# RibbonCable.net
KiCad netlist of a schematic drawn in Altium Designer
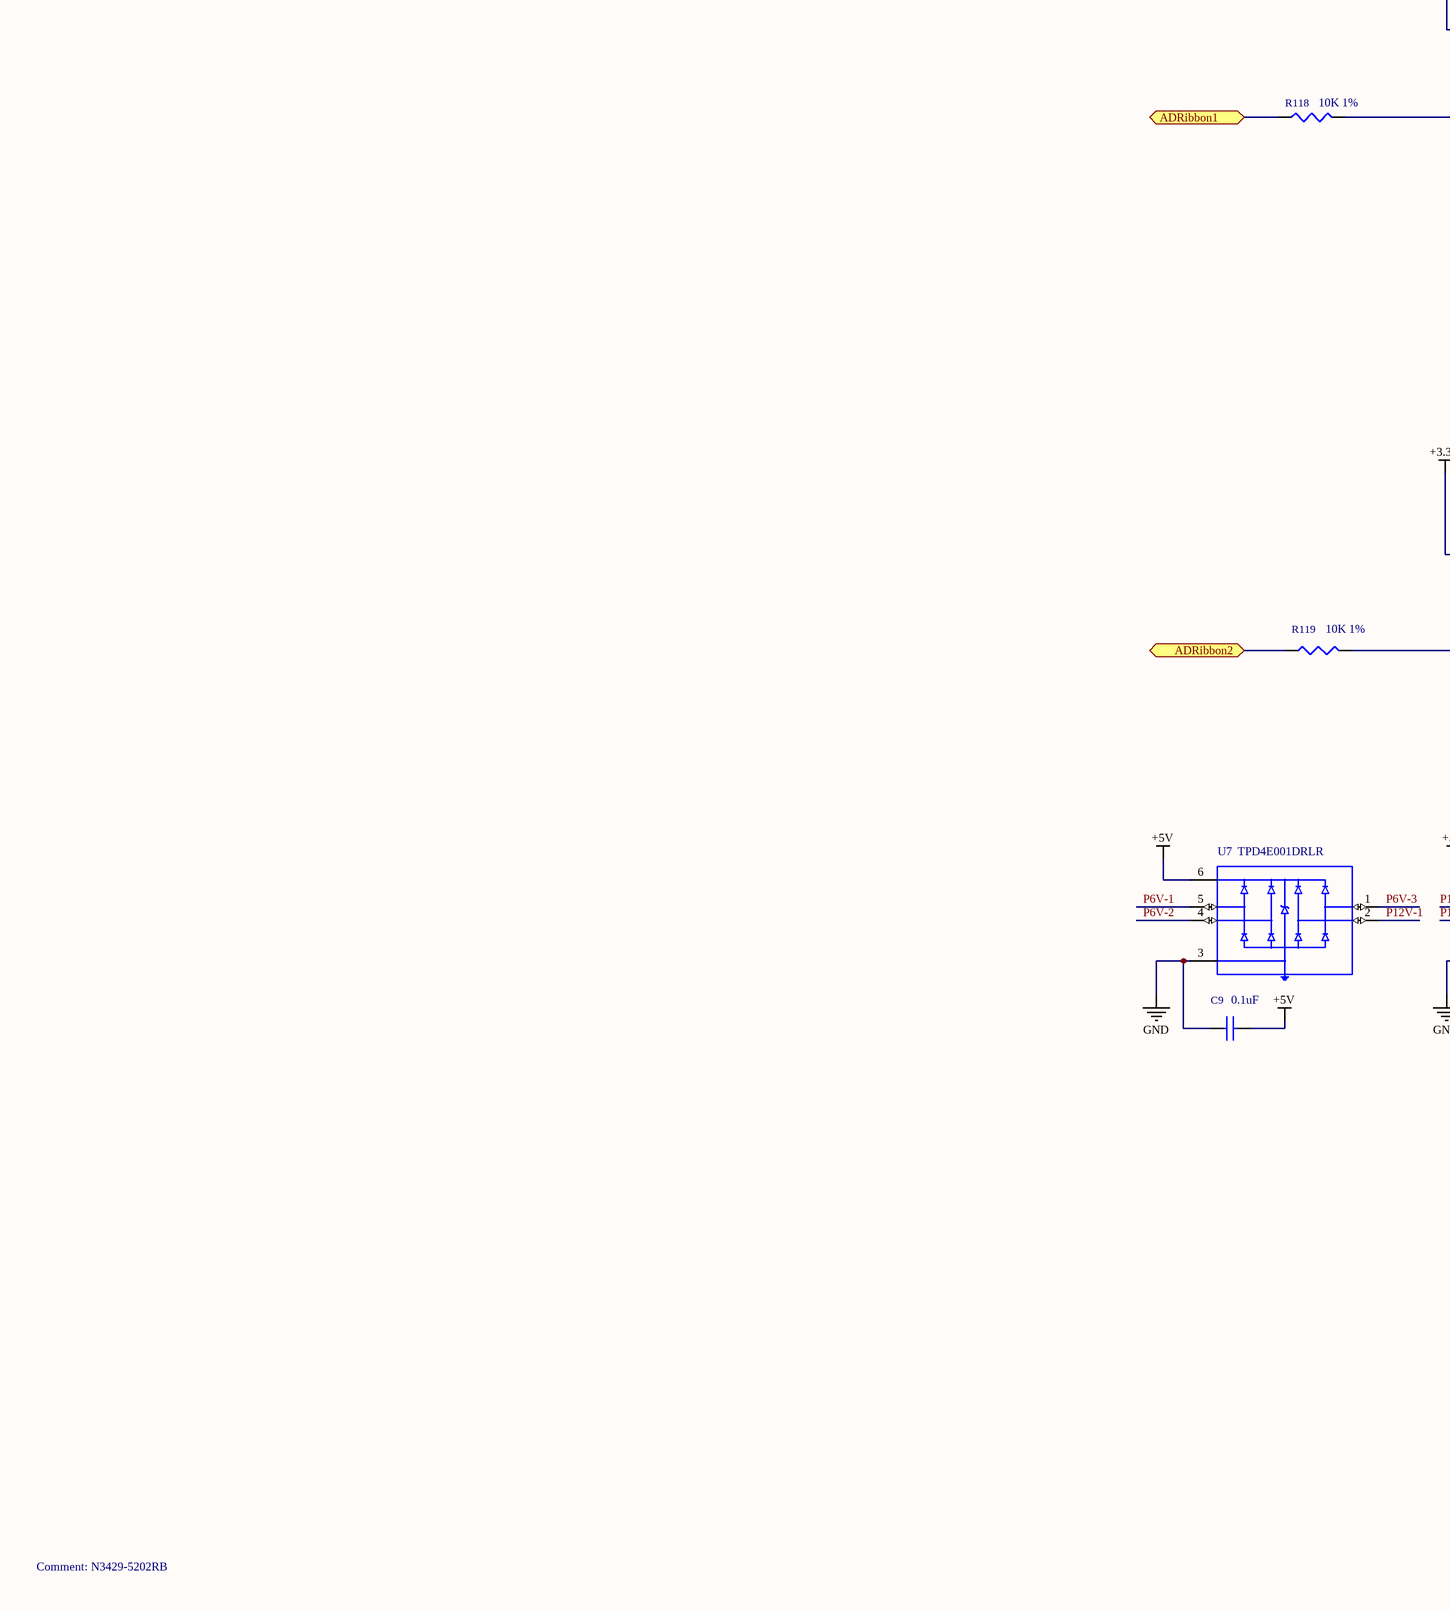
[diagram p0: RibbonCable.SchDoc, left]
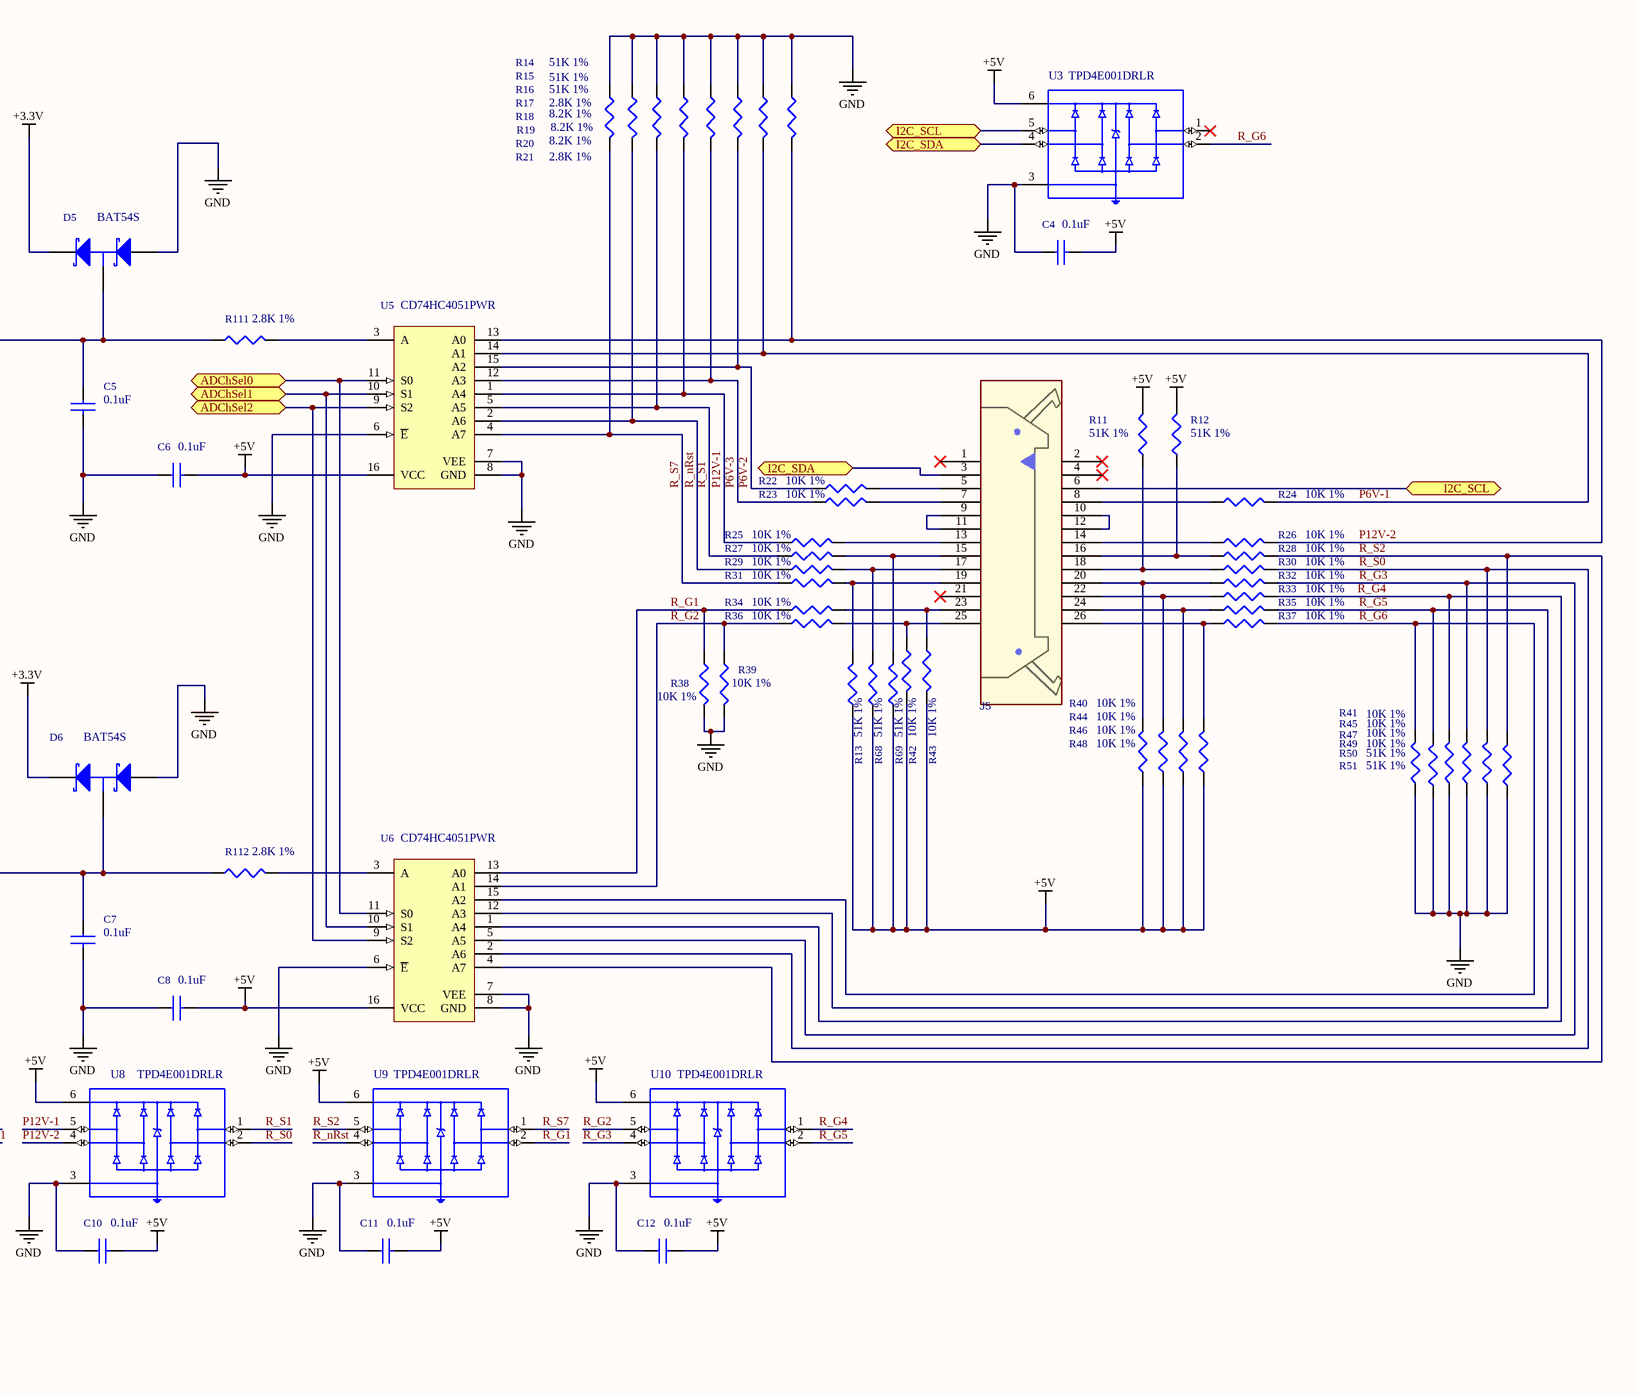
[diagram p1: RibbonCable.SchDoc, right]

(export (version "E")
  (design (tool "Eeschema 10.0.6"))
  (components
    (comp (ref "C4")
      (value "0.1uF")
      (footprint "C0402")
      (description "Cap Ceramic 0.1uF 50V X7R 10% Pad SMD 0402 125C Automotive T/R")
      (fields
        (field (name "MANUFACTURER") "Murata")
        (field (name "MANUFACTURER PART NUMBER") "GRT155R71H104KE01D")
      )
      (libsource (lib "Leo-Home-SQL-Lib") (part "CAPNP"))
    )
    (comp (ref "C5")
      (value "0.1uF")
      (footprint "C0402")
      (description "Cap Ceramic 0.1uF 50V X7R 10% Pad SMD 0402 125C Automotive T/R")
      (fields
        (field (name "MANUFACTURER") "Murata")
        (field (name "MANUFACTURER PART NUMBER") "GRT155R71H104KE01D")
      )
      (libsource (lib "Leo-Home-SQL-Lib") (part "CAPNP"))
    )
    (comp (ref "C6")
      (value "0.1uF")
      (footprint "C0402")
      (description "Cap Ceramic 0.1uF 50V X7R 10% Pad SMD 0402 125C Automotive T/R")
      (fields
        (field (name "MANUFACTURER") "Murata")
        (field (name "MANUFACTURER PART NUMBER") "GRT155R71H104KE01D")
      )
      (libsource (lib "Leo-Home-SQL-Lib") (part "CAPNP"))
    )
    (comp (ref "C7")
      (value "0.1uF")
      (footprint "C0402")
      (description "Cap Ceramic 0.1uF 50V X7R 10% Pad SMD 0402 125C Automotive T/R")
      (fields
        (field (name "MANUFACTURER") "Murata")
        (field (name "MANUFACTURER PART NUMBER") "GRT155R71H104KE01D")
      )
      (libsource (lib "Leo-Home-SQL-Lib") (part "CAPNP"))
    )
    (comp (ref "C8")
      (value "0.1uF")
      (footprint "C0402")
      (description "Cap Ceramic 0.1uF 50V X7R 10% Pad SMD 0402 125C Automotive T/R")
      (fields
        (field (name "MANUFACTURER") "Murata")
        (field (name "MANUFACTURER PART NUMBER") "GRT155R71H104KE01D")
      )
      (libsource (lib "Leo-Home-SQL-Lib") (part "CAPNP"))
    )
    (comp (ref "C9")
      (value "0.1uF")
      (footprint "C0402")
      (description "Cap Ceramic 0.1uF 50V X7R 10% Pad SMD 0402 125C Automotive T/R")
      (fields
        (field (name "MANUFACTURER") "Murata")
        (field (name "MANUFACTURER PART NUMBER") "GRT155R71H104KE01D")
      )
      (libsource (lib "Leo-Home-SQL-Lib") (part "CAPNP"))
    )
    (comp (ref "C10")
      (value "0.1uF")
      (footprint "C0402")
      (description "Cap Ceramic 0.1uF 50V X7R 10% Pad SMD 0402 125C Automotive T/R")
      (fields
        (field (name "MANUFACTURER") "Murata")
        (field (name "MANUFACTURER PART NUMBER") "GRT155R71H104KE01D")
      )
      (libsource (lib "Leo-Home-SQL-Lib") (part "CAPNP"))
    )
    (comp (ref "C11")
      (value "0.1uF")
      (footprint "C0402")
      (description "Cap Ceramic 0.1uF 50V X7R 10% Pad SMD 0402 125C Automotive T/R")
      (fields
        (field (name "MANUFACTURER") "Murata")
        (field (name "MANUFACTURER PART NUMBER") "GRT155R71H104KE01D")
      )
      (libsource (lib "Leo-Home-SQL-Lib") (part "CAPNP"))
    )
    (comp (ref "C12")
      (value "0.1uF")
      (footprint "C0402")
      (description "Cap Ceramic 0.1uF 50V X7R 10% Pad SMD 0402 125C Automotive T/R")
      (fields
        (field (name "MANUFACTURER") "Murata")
        (field (name "MANUFACTURER PART NUMBER") "GRT155R71H104KE01D")
      )
      (libsource (lib "Leo-Home-SQL-Lib") (part "CAPNP"))
    )
    (comp (ref "D5")
      (value "BAT54S")
      (footprint "sot23-3")
      (description "DIODE SCHOTTKY 30V 150MA SOT23-3")
      (fields
        (field (name "MANUFACTURER") "Sangdest Microelectronics")
        (field (name "MANUFACTURER_1") "ON Semiconductor / Fairchild")
      )
      (libsource (lib "Leo-Home-SQL-Lib") (part "BAT54S-7-F"))
    )
    (comp (ref "D6")
      (value "BAT54S")
      (footprint "sot23-3")
      (description "DIODE SCHOTTKY 30V 150MA SOT23-3")
      (fields
        (field (name "MANUFACTURER") "Sangdest Microelectronics")
        (field (name "MANUFACTURER_1") "ON Semiconductor / Fairchild")
      )
      (libsource (lib "Leo-Home-SQL-Lib") (part "BAT54S-7-F"))
    )
    (comp (ref "J5")
      (value "N3429-5202RB")
      (footprint "CONN_N3429-5202RB")
      (description "3000 Series; 2.54mm Pitch 26 Way 2 Row Right")
      (fields (field (name "MANUFACTURER") "3M") (field (name "VOLTAGE") "300V"))
      (libsource (lib "Leo-Home-SQL-Lib") (part "CN_100_26POS_13x2_RTA_LATCH"))
    )
    (comp (ref "R11")
      (value "51K 1%")
      (footprint "R0402")
      (description "Res Thick Film 0402 51K Ohm 1% 0.063W(1/16W) ±100ppm/C Pad SMD Automotive T/R")
      (fields
        (field (name "MANUFACTURER") "Stackpole Electronics")
        (field (name "MANUFACTURER PART NUMBER") "RMCF0402FT51K0")
      )
      (libsource (lib "Leo-Home-SQL-Lib") (part "Resistor"))
    )
    (comp (ref "R12")
      (value "51K 1%")
      (footprint "R0402")
      (description "Res Thick Film 0402 51K Ohm 1% 0.063W(1/16W) ±100ppm/C Pad SMD Automotive T/R")
      (fields
        (field (name "MANUFACTURER") "Stackpole Electronics")
        (field (name "MANUFACTURER PART NUMBER") "RMCF0402FT51K0")
      )
      (libsource (lib "Leo-Home-SQL-Lib") (part "Resistor"))
    )
    (comp (ref "R13")
      (value "51K 1%")
      (footprint "R0402")
      (description "Res Thick Film 0402 51K Ohm 1% 0.063W(1/16W) ±100ppm/C Pad SMD Automotive T/R")
      (fields
        (field (name "MANUFACTURER") "Stackpole Electronics")
        (field (name "MANUFACTURER PART NUMBER") "RMCF0402FT51K0")
      )
      (libsource (lib "Leo-Home-SQL-Lib") (part "Resistor"))
    )
    (comp (ref "R14")
      (value "51K 1%")
      (footprint "R0402")
      (description "Res Thick Film 0402 51K Ohm 1% 0.063W(1/16W) ±100ppm/C Pad SMD Automotive T/R")
      (fields
        (field (name "MANUFACTURER") "Stackpole Electronics")
        (field (name "MANUFACTURER PART NUMBER") "RMCF0402FT51K0")
      )
      (libsource (lib "Leo-Home-SQL-Lib") (part "Resistor"))
    )
    (comp (ref "R15")
      (value "51K 1%")
      (footprint "R0402")
      (description "Res Thick Film 0402 51K Ohm 1% 0.063W(1/16W) ±100ppm/C Pad SMD Automotive T/R")
      (fields
        (field (name "MANUFACTURER") "Stackpole Electronics")
        (field (name "MANUFACTURER PART NUMBER") "RMCF0402FT51K0")
      )
      (libsource (lib "Leo-Home-SQL-Lib") (part "Resistor"))
    )
    (comp (ref "R16")
      (value "51K 1%")
      (footprint "R0402")
      (description "Res Thick Film 0402 51K Ohm 1% 0.063W(1/16W) ±100ppm/C Pad SMD Automotive T/R")
      (fields
        (field (name "MANUFACTURER") "Stackpole Electronics")
        (field (name "MANUFACTURER PART NUMBER") "RMCF0402FT51K0")
      )
      (libsource (lib "Leo-Home-SQL-Lib") (part "Resistor"))
    )
    (comp (ref "R17")
      (value "2.8K 1%")
      (footprint "R0402")
      (description "Thick Film 0402 2.8K Ohm 1% 0.063W ±100ppm/°C Molded SMD Paper T/R")
      (fields
        (field (name "MANUFACTURER") "Stackpole Electronics")
        (field (name "MANUFACTURER PART NUMBER") "RMCF0402FT2K80")
      )
      (libsource (lib "Leo-Home-SQL-Lib") (part "Resistor"))
    )
    (comp (ref "R18")
      (value "8.2K 1%")
      (footprint "R0402")
      (description "Res Thick Film 0402 8.2K Ohm 5% 0.063W ±100ppm/°C Molded SMD Paper T/R")
      (fields
        (field (name "MANUFACTURER") "Stackpole Electronics")
        (field (name "MANUFACTURER PART NUMBER") "RMCF0402JT8K20")
      )
      (libsource (lib "Leo-Home-SQL-Lib") (part "Resistor"))
    )
    (comp (ref "R19")
      (value "8.2K 1%")
      (footprint "R0402")
      (description "Res Thick Film 0402 8.2K Ohm 5% 0.063W ±100ppm/°C Molded SMD Paper T/R")
      (fields
        (field (name "MANUFACTURER") "Stackpole Electronics")
        (field (name "MANUFACTURER PART NUMBER") "RMCF0402JT8K20")
      )
      (libsource (lib "Leo-Home-SQL-Lib") (part "Resistor"))
    )
    (comp (ref "R20")
      (value "8.2K 1%")
      (footprint "R0402")
      (description "Res Thick Film 0402 8.2K Ohm 5% 0.063W ±100ppm/°C Molded SMD Paper T/R")
      (fields
        (field (name "MANUFACTURER") "Stackpole Electronics")
        (field (name "MANUFACTURER PART NUMBER") "RMCF0402JT8K20")
      )
      (libsource (lib "Leo-Home-SQL-Lib") (part "Resistor"))
    )
    (comp (ref "R21")
      (value "2.8K 1%")
      (footprint "R0402")
      (description "Thick Film 0402 2.8K Ohm 1% 0.063W ±100ppm/°C Molded SMD Paper T/R")
      (fields
        (field (name "MANUFACTURER") "Stackpole Electronics")
        (field (name "MANUFACTURER PART NUMBER") "RMCF0402FT2K80")
      )
      (libsource (lib "Leo-Home-SQL-Lib") (part "Resistor"))
    )
    (comp (ref "R22")
      (value "10K 1%")
      (footprint "R0402")
      (description "Thick Film 0402 10K OHM 1% 1/16W 0402")
      (fields
        (field (name "MANUFACTURER") "Yageo")
        (field (name "MANUFACTURER PART NUMBER") "RC0402FR-0710KP")
      )
      (libsource (lib "Leo-Home-SQL-Lib") (part "Resistor"))
    )
    (comp (ref "R23")
      (value "10K 1%")
      (footprint "R0402")
      (description "Thick Film 0402 10K OHM 1% 1/16W 0402")
      (fields
        (field (name "MANUFACTURER") "Yageo")
        (field (name "MANUFACTURER PART NUMBER") "RC0402FR-0710KP")
      )
      (libsource (lib "Leo-Home-SQL-Lib") (part "Resistor"))
    )
    (comp (ref "R24")
      (value "10K 1%")
      (footprint "R0402")
      (description "Thick Film 0402 10K OHM 1% 1/16W 0402")
      (fields
        (field (name "MANUFACTURER") "Yageo")
        (field (name "MANUFACTURER PART NUMBER") "RC0402FR-0710KP")
      )
      (libsource (lib "Leo-Home-SQL-Lib") (part "Resistor"))
    )
    (comp (ref "R25")
      (value "10K 1%")
      (footprint "R0402")
      (description "Thick Film 0402 10K OHM 1% 1/16W 0402")
      (fields
        (field (name "MANUFACTURER") "Yageo")
        (field (name "MANUFACTURER PART NUMBER") "RC0402FR-0710KP")
      )
      (libsource (lib "Leo-Home-SQL-Lib") (part "Resistor"))
    )
    (comp (ref "R26")
      (value "10K 1%")
      (footprint "R0402")
      (description "Thick Film 0402 10K OHM 1% 1/16W 0402")
      (fields
        (field (name "MANUFACTURER") "Yageo")
        (field (name "MANUFACTURER PART NUMBER") "RC0402FR-0710KP")
      )
      (libsource (lib "Leo-Home-SQL-Lib") (part "Resistor"))
    )
    (comp (ref "R27")
      (value "10K 1%")
      (footprint "R0402")
      (description "Thick Film 0402 10K OHM 1% 1/16W 0402")
      (fields
        (field (name "MANUFACTURER") "Yageo")
        (field (name "MANUFACTURER PART NUMBER") "RC0402FR-0710KP")
      )
      (libsource (lib "Leo-Home-SQL-Lib") (part "Resistor"))
    )
    (comp (ref "R28")
      (value "10K 1%")
      (footprint "R0402")
      (description "Thick Film 0402 10K OHM 1% 1/16W 0402")
      (fields
        (field (name "MANUFACTURER") "Yageo")
        (field (name "MANUFACTURER PART NUMBER") "RC0402FR-0710KP")
      )
      (libsource (lib "Leo-Home-SQL-Lib") (part "Resistor"))
    )
    (comp (ref "R29")
      (value "10K 1%")
      (footprint "R0402")
      (description "Thick Film 0402 10K OHM 1% 1/16W 0402")
      (fields
        (field (name "MANUFACTURER") "Yageo")
        (field (name "MANUFACTURER PART NUMBER") "RC0402FR-0710KP")
      )
      (libsource (lib "Leo-Home-SQL-Lib") (part "Resistor"))
    )
    (comp (ref "R30")
      (value "10K 1%")
      (footprint "R0402")
      (description "Thick Film 0402 10K OHM 1% 1/16W 0402")
      (fields
        (field (name "MANUFACTURER") "Yageo")
        (field (name "MANUFACTURER PART NUMBER") "RC0402FR-0710KP")
      )
      (libsource (lib "Leo-Home-SQL-Lib") (part "Resistor"))
    )
    (comp (ref "R31")
      (value "10K 1%")
      (footprint "R0402")
      (description "Thick Film 0402 10K OHM 1% 1/16W 0402")
      (fields
        (field (name "MANUFACTURER") "Yageo")
        (field (name "MANUFACTURER PART NUMBER") "RC0402FR-0710KP")
      )
      (libsource (lib "Leo-Home-SQL-Lib") (part "Resistor"))
    )
    (comp (ref "R32")
      (value "10K 1%")
      (footprint "R0402")
      (description "Thick Film 0402 10K OHM 1% 1/16W 0402")
      (fields
        (field (name "MANUFACTURER") "Yageo")
        (field (name "MANUFACTURER PART NUMBER") "RC0402FR-0710KP")
      )
      (libsource (lib "Leo-Home-SQL-Lib") (part "Resistor"))
    )
    (comp (ref "R33")
      (value "10K 1%")
      (footprint "R0402")
      (description "Thick Film 0402 10K OHM 1% 1/16W 0402")
      (fields
        (field (name "MANUFACTURER") "Yageo")
        (field (name "MANUFACTURER PART NUMBER") "RC0402FR-0710KP")
      )
      (libsource (lib "Leo-Home-SQL-Lib") (part "Resistor"))
    )
    (comp (ref "R34")
      (value "10K 1%")
      (footprint "R0402")
      (description "Thick Film 0402 10K OHM 1% 1/16W 0402")
      (fields
        (field (name "MANUFACTURER") "Yageo")
        (field (name "MANUFACTURER PART NUMBER") "RC0402FR-0710KP")
      )
      (libsource (lib "Leo-Home-SQL-Lib") (part "Resistor"))
    )
    (comp (ref "R35")
      (value "10K 1%")
      (footprint "R0402")
      (description "Thick Film 0402 10K OHM 1% 1/16W 0402")
      (fields
        (field (name "MANUFACTURER") "Yageo")
        (field (name "MANUFACTURER PART NUMBER") "RC0402FR-0710KP")
      )
      (libsource (lib "Leo-Home-SQL-Lib") (part "Resistor"))
    )
    (comp (ref "R36")
      (value "10K 1%")
      (footprint "R0402")
      (description "Thick Film 0402 10K OHM 1% 1/16W 0402")
      (fields
        (field (name "MANUFACTURER") "Yageo")
        (field (name "MANUFACTURER PART NUMBER") "RC0402FR-0710KP")
      )
      (libsource (lib "Leo-Home-SQL-Lib") (part "Resistor"))
    )
    (comp (ref "R37")
      (value "10K 1%")
      (footprint "R0402")
      (description "Thick Film 0402 10K OHM 1% 1/16W 0402")
      (fields
        (field (name "MANUFACTURER") "Yageo")
        (field (name "MANUFACTURER PART NUMBER") "RC0402FR-0710KP")
      )
      (libsource (lib "Leo-Home-SQL-Lib") (part "Resistor"))
    )
    (comp (ref "R38")
      (value "10K 1%")
      (footprint "R0402")
      (description "Thick Film 0402 10K OHM 1% 1/16W 0402")
      (fields
        (field (name "MANUFACTURER") "Yageo")
        (field (name "MANUFACTURER PART NUMBER") "RC0402FR-0710KP")
      )
      (libsource (lib "Leo-Home-SQL-Lib") (part "Resistor"))
    )
    (comp (ref "R39")
      (value "10K 1%")
      (footprint "R0402")
      (description "Thick Film 0402 10K OHM 1% 1/16W 0402")
      (fields
        (field (name "MANUFACTURER") "Yageo")
        (field (name "MANUFACTURER PART NUMBER") "RC0402FR-0710KP")
      )
      (libsource (lib "Leo-Home-SQL-Lib") (part "Resistor"))
    )
    (comp (ref "R40")
      (value "10K 1%")
      (footprint "R0402")
      (description "Thick Film 0402 10K OHM 1% 1/16W 0402")
      (fields
        (field (name "MANUFACTURER") "Yageo")
        (field (name "MANUFACTURER PART NUMBER") "RC0402FR-0710KP")
      )
      (libsource (lib "Leo-Home-SQL-Lib") (part "Resistor"))
    )
    (comp (ref "R41")
      (value "10K 1%")
      (footprint "R0402")
      (description "Thick Film 0402 10K OHM 1% 1/16W 0402")
      (fields
        (field (name "MANUFACTURER") "Yageo")
        (field (name "MANUFACTURER PART NUMBER") "RC0402FR-0710KP")
      )
      (libsource (lib "Leo-Home-SQL-Lib") (part "Resistor"))
    )
    (comp (ref "R42")
      (value "10K 1%")
      (footprint "R0402")
      (description "Thick Film 0402 10K OHM 1% 1/16W 0402")
      (fields
        (field (name "MANUFACTURER") "Yageo")
        (field (name "MANUFACTURER PART NUMBER") "RC0402FR-0710KP")
      )
      (libsource (lib "Leo-Home-SQL-Lib") (part "Resistor"))
    )
    (comp (ref "R43")
      (value "10K 1%")
      (footprint "R0402")
      (description "Thick Film 0402 10K OHM 1% 1/16W 0402")
      (fields
        (field (name "MANUFACTURER") "Yageo")
        (field (name "MANUFACTURER PART NUMBER") "RC0402FR-0710KP")
      )
      (libsource (lib "Leo-Home-SQL-Lib") (part "Resistor"))
    )
    (comp (ref "R44")
      (value "10K 1%")
      (footprint "R0402")
      (description "Thick Film 0402 10K OHM 1% 1/16W 0402")
      (fields
        (field (name "MANUFACTURER") "Yageo")
        (field (name "MANUFACTURER PART NUMBER") "RC0402FR-0710KP")
      )
      (libsource (lib "Leo-Home-SQL-Lib") (part "Resistor"))
    )
    (comp (ref "R45")
      (value "10K 1%")
      (footprint "R0402")
      (description "Thick Film 0402 10K OHM 1% 1/16W 0402")
      (fields
        (field (name "MANUFACTURER") "Yageo")
        (field (name "MANUFACTURER PART NUMBER") "RC0402FR-0710KP")
      )
      (libsource (lib "Leo-Home-SQL-Lib") (part "Resistor"))
    )
    (comp (ref "R46")
      (value "10K 1%")
      (footprint "R0402")
      (description "Thick Film 0402 10K OHM 1% 1/16W 0402")
      (fields
        (field (name "MANUFACTURER") "Yageo")
        (field (name "MANUFACTURER PART NUMBER") "RC0402FR-0710KP")
      )
      (libsource (lib "Leo-Home-SQL-Lib") (part "Resistor"))
    )
    (comp (ref "R47")
      (value "10K 1%")
      (footprint "R0402")
      (description "Thick Film 0402 10K OHM 1% 1/16W 0402")
      (fields
        (field (name "MANUFACTURER") "Yageo")
        (field (name "MANUFACTURER PART NUMBER") "RC0402FR-0710KP")
      )
      (libsource (lib "Leo-Home-SQL-Lib") (part "Resistor"))
    )
    (comp (ref "R48")
      (value "10K 1%")
      (footprint "R0402")
      (description "Thick Film 0402 10K OHM 1% 1/16W 0402")
      (fields
        (field (name "MANUFACTURER") "Yageo")
        (field (name "MANUFACTURER PART NUMBER") "RC0402FR-0710KP")
      )
      (libsource (lib "Leo-Home-SQL-Lib") (part "Resistor"))
    )
    (comp (ref "R49")
      (value "10K 1%")
      (footprint "R0402")
      (description "Thick Film 0402 10K OHM 1% 1/16W 0402")
      (fields
        (field (name "MANUFACTURER") "Yageo")
        (field (name "MANUFACTURER PART NUMBER") "RC0402FR-0710KP")
      )
      (libsource (lib "Leo-Home-SQL-Lib") (part "Resistor"))
    )
    (comp (ref "R50")
      (value "51K 1%")
      (footprint "R0402")
      (description "Res Thick Film 0402 51K Ohm 1% 0.063W(1/16W) ±100ppm/C Pad SMD Automotive T/R")
      (fields
        (field (name "MANUFACTURER") "Stackpole Electronics")
        (field (name "MANUFACTURER PART NUMBER") "RMCF0402FT51K0")
      )
      (libsource (lib "Leo-Home-SQL-Lib") (part "Resistor"))
    )
    (comp (ref "R51")
      (value "51K 1%")
      (footprint "R0402")
      (description "Res Thick Film 0402 51K Ohm 1% 0.063W(1/16W) ±100ppm/C Pad SMD Automotive T/R")
      (fields
        (field (name "MANUFACTURER") "Stackpole Electronics")
        (field (name "MANUFACTURER PART NUMBER") "RMCF0402FT51K0")
      )
      (libsource (lib "Leo-Home-SQL-Lib") (part "Resistor"))
    )
    (comp (ref "R68")
      (value "51K 1%")
      (footprint "R0402")
      (description "Res Thick Film 0402 51K Ohm 1% 0.063W(1/16W) ±100ppm/C Pad SMD Automotive T/R")
      (fields
        (field (name "MANUFACTURER") "Stackpole Electronics")
        (field (name "MANUFACTURER PART NUMBER") "RMCF0402FT51K0")
      )
      (libsource (lib "Leo-Home-SQL-Lib") (part "Resistor"))
    )
    (comp (ref "R69")
      (value "51K 1%")
      (footprint "R0402")
      (description "Res Thick Film 0402 51K Ohm 1% 0.063W(1/16W) ±100ppm/C Pad SMD Automotive T/R")
      (fields
        (field (name "MANUFACTURER") "Stackpole Electronics")
        (field (name "MANUFACTURER PART NUMBER") "RMCF0402FT51K0")
      )
      (libsource (lib "Leo-Home-SQL-Lib") (part "Resistor"))
    )
    (comp (ref "R111")
      (value "2.8K 1%")
      (footprint "R0402")
      (description "Thick Film 0402 2.8K Ohm 1% 0.063W ±100ppm/°C Molded SMD Paper T/R")
      (fields
        (field (name "MANUFACTURER") "Stackpole Electronics")
        (field (name "MANUFACTURER PART NUMBER") "RMCF0402FT2K80")
      )
      (libsource (lib "Leo-Home-SQL-Lib") (part "Resistor"))
    )
    (comp (ref "R112")
      (value "2.8K 1%")
      (footprint "R0402")
      (description "Thick Film 0402 2.8K Ohm 1% 0.063W ±100ppm/°C Molded SMD Paper T/R")
      (fields
        (field (name "MANUFACTURER") "Stackpole Electronics")
        (field (name "MANUFACTURER PART NUMBER") "RMCF0402FT2K80")
      )
      (libsource (lib "Leo-Home-SQL-Lib") (part "Resistor"))
    )
    (comp (ref "R118")
      (value "10K 1%")
      (footprint "R0402")
      (description "Thick Film 0402 10K OHM 1% 1/16W 0402")
      (fields
        (field (name "MANUFACTURER") "Yageo")
        (field (name "MANUFACTURER PART NUMBER") "RC0402FR-0710KP")
      )
      (libsource (lib "Leo-Home-SQL-Lib") (part "Resistor"))
    )
    (comp (ref "R119")
      (value "10K 1%")
      (footprint "R0402")
      (description "Thick Film 0402 10K OHM 1% 1/16W 0402")
      (fields
        (field (name "MANUFACTURER") "Yageo")
        (field (name "MANUFACTURER PART NUMBER") "RC0402FR-0710KP")
      )
      (libsource (lib "Leo-Home-SQL-Lib") (part "Resistor"))
    )
    (comp (ref "U3")
      (value "TPD4E001DRLR")
      (footprint "SOTFL50P160X60-6N")
      (description "TVS DIODE 5.5VWM SOT6")
      (fields (field (name "MANUFACTURER") "Texas Instruments") (field (name "LCSC PART NUMBER") "C527516"))
      (libsource (lib "Leo-Home-SQL-Lib") (part "TPD4E001DRLR"))
    )
    (comp (ref "U5")
      (value "CD74HC4051PWR")
      (footprint "16-TSSOP-4.4mm")
      (description "5-V, 8: 1, 1-channel analog mutliplexer 16-TS")
      (fields
        (field (name "GENERIC PART NUMBER") "CD74HC4051")
        (field (name "MANUFACTURER") "Texas Instruments")
      )
      (libsource (lib "Leo-Home-SQL-Lib") (part "CMP-1575-00038-4_1"))
    )
    (comp (ref "U6")
      (value "CD74HC4051PWR")
      (footprint "16-TSSOP-4.4mm")
      (description "5-V, 8: 1, 1-channel analog mutliplexer 16-TS")
      (fields
        (field (name "GENERIC PART NUMBER") "CD74HC4051")
        (field (name "MANUFACTURER") "Texas Instruments")
      )
      (libsource (lib "Leo-Home-SQL-Lib") (part "CMP-1575-00038-4_1"))
    )
    (comp (ref "U7")
      (value "TPD4E001DRLR")
      (footprint "SOTFL50P160X60-6N")
      (description "TVS DIODE 5.5VWM SOT6")
      (fields (field (name "MANUFACTURER") "Texas Instruments") (field (name "LCSC PART NUMBER") "C527516"))
      (libsource (lib "Leo-Home-SQL-Lib") (part "TPD4E001DRLR"))
    )
    (comp (ref "U8")
      (value "TPD4E001DRLR")
      (footprint "SOTFL50P160X60-6N")
      (description "TVS DIODE 5.5VWM SOT6")
      (fields (field (name "MANUFACTURER") "Texas Instruments") (field (name "LCSC PART NUMBER") "C527516"))
      (libsource (lib "Leo-Home-SQL-Lib") (part "TPD4E001DRLR"))
    )
    (comp (ref "U9")
      (value "TPD4E001DRLR")
      (footprint "SOTFL50P160X60-6N")
      (description "TVS DIODE 5.5VWM SOT6")
      (fields (field (name "MANUFACTURER") "Texas Instruments") (field (name "LCSC PART NUMBER") "C527516"))
      (libsource (lib "Leo-Home-SQL-Lib") (part "TPD4E001DRLR"))
    )
    (comp (ref "U10")
      (value "TPD4E001DRLR")
      (footprint "SOTFL50P160X60-6N")
      (description "TVS DIODE 5.5VWM SOT6")
      (fields (field (name "MANUFACTURER") "Texas Instruments") (field (name "LCSC PART NUMBER") "C527516"))
      (libsource (lib "Leo-Home-SQL-Lib") (part "TPD4E001DRLR"))
    )
  )
  (nets
    (net (code "1") (name "+3.3V") (class "Default")
      (node (ref "D5") (pin "2") (pinfunction "K_2") (pintype "passive"))
      (node (ref "D6") (pin "2") (pinfunction "K_2") (pintype "passive"))
    )
    (net (code "2") (name "+5V") (class "Default")
      (node (ref "C10") (pin "2") (pinfunction "2_2") (pintype "passive"))
      (node (ref "C11") (pin "2") (pinfunction "2_2") (pintype "passive"))
      (node (ref "C12") (pin "2") (pinfunction "2_2") (pintype "passive"))
      (node (ref "C4") (pin "2") (pinfunction "2_2") (pintype "passive"))
      (node (ref "C6") (pin "2") (pinfunction "2_2") (pintype "passive"))
      (node (ref "C8") (pin "2") (pinfunction "2_2") (pintype "passive"))
      (node (ref "C9") (pin "2") (pinfunction "2_2") (pintype "passive"))
      (node (ref "R11") (pin "2") (pinfunction "2_2") (pintype "passive"))
      (node (ref "R12") (pin "2") (pinfunction "2_2") (pintype "passive"))
      (node (ref "R13") (pin "1") (pinfunction "1_1") (pintype "passive"))
      (node (ref "R40") (pin "1") (pinfunction "1_1") (pintype "passive"))
      (node (ref "R42") (pin "2") (pinfunction "2_2") (pintype "passive"))
      (node (ref "R43") (pin "2") (pinfunction "2_2") (pintype "passive"))
      (node (ref "R44") (pin "1") (pinfunction "1_1") (pintype "passive"))
      (node (ref "R46") (pin "1") (pinfunction "1_1") (pintype "passive"))
      (node (ref "R48") (pin "1") (pinfunction "1_1") (pintype "passive"))
      (node (ref "R68") (pin "1") (pinfunction "1_1") (pintype "passive"))
      (node (ref "R69") (pin "1") (pinfunction "1_1") (pintype "passive"))
      (node (ref "U10") (pin "6") (pinfunction "VCC_6") (pintype "power_in"))
      (node (ref "U3") (pin "6") (pinfunction "VCC_6") (pintype "power_in"))
      (node (ref "U5") (pin "16") (pinfunction "VCC_16") (pintype "power_in"))
      (node (ref "U6") (pin "16") (pinfunction "VCC_16") (pintype "power_in"))
      (node (ref "U7") (pin "6") (pinfunction "VCC_6") (pintype "power_in"))
      (node (ref "U8") (pin "6") (pinfunction "VCC_6") (pintype "power_in"))
      (node (ref "U9") (pin "6") (pinfunction "VCC_6") (pintype "power_in"))
    )
    (net (code "3") (name "/ADChSel0") (class "Default")
      (node (ref "U5") (pin "11") (pinfunction "S0_11") (pintype "input"))
      (node (ref "U6") (pin "11") (pinfunction "S0_11") (pintype "input"))
    )
    (net (code "4") (name "/ADChSel1") (class "Default")
      (node (ref "U5") (pin "10") (pinfunction "S1_10") (pintype "input"))
      (node (ref "U6") (pin "10") (pinfunction "S1_10") (pintype "input"))
    )
    (net (code "5") (name "/ADChSel2") (class "Default")
      (node (ref "U5") (pin "9") (pinfunction "S2_9") (pintype "input"))
      (node (ref "U6") (pin "9") (pinfunction "S2_9") (pintype "input"))
    )
    (net (code "6") (name "/ADRibbon1") (class "Default")
      (node (ref "R118") (pin "1") (pinfunction "1_1") (pintype "passive"))
    )
    (net (code "7") (name "/ADRibbon2") (class "Default")
      (node (ref "R119") (pin "1") (pinfunction "1_1") (pintype "passive"))
    )
    (net (code "8") (name "/I2C_SCL") (class "Default")
      (node (ref "J5") (pin "6") (pinfunction "6_6") (pintype "passive"))
      (node (ref "U3") (pin "5") (pinfunction "IO4_5") (pintype "bidirectional"))
    )
    (net (code "9") (name "/I2C_SDA") (class "Default")
      (node (ref "J5") (pin "3") (pinfunction "3_3") (pintype "passive"))
      (node (ref "U3") (pin "4") (pinfunction "IO3_4") (pintype "bidirectional"))
    )
    (net (code "10") (name "/P6V-1") (class "Default")
      (node (ref "R20") (pin "2") (pinfunction "2_2") (pintype "passive"))
      (node (ref "R24") (pin "2") (pinfunction "2_2") (pintype "passive"))
      (node (ref "U5") (pin "14") (pinfunction "A1_14") (pintype "passive"))
      (node (ref "U7") (pin "5") (pinfunction "IO4_5") (pintype "bidirectional"))
    )
    (net (code "11") (name "/P6V-2") (class "Default")
      (node (ref "R19") (pin "2") (pinfunction "2_2") (pintype "passive"))
      (node (ref "R22") (pin "1") (pinfunction "1_1") (pintype "passive"))
      (node (ref "U5") (pin "15") (pinfunction "A2_15") (pintype "passive"))
      (node (ref "U7") (pin "4") (pinfunction "IO3_4") (pintype "bidirectional"))
    )
    (net (code "12") (name "/P6V-3") (class "Default")
      (node (ref "R18") (pin "2") (pinfunction "2_2") (pintype "passive"))
      (node (ref "R23") (pin "1") (pinfunction "1_1") (pintype "passive"))
      (node (ref "U5") (pin "12") (pinfunction "A3_12") (pintype "passive"))
      (node (ref "U7") (pin "1") (pinfunction "IO1_1") (pintype "bidirectional"))
    )
    (net (code "13") (name "/P12V-1") (class "Default")
      (node (ref "R17") (pin "2") (pinfunction "2_2") (pintype "passive"))
      (node (ref "R25") (pin "1") (pinfunction "1_1") (pintype "passive"))
      (node (ref "U5") (pin "1") (pinfunction "A4_1") (pintype "passive"))
      (node (ref "U7") (pin "2") (pinfunction "IO2_2") (pintype "bidirectional"))
      (node (ref "U8") (pin "5") (pinfunction "IO4_5") (pintype "bidirectional"))
    )
    (net (code "14") (name "/P12V-2") (class "Default")
      (node (ref "R21") (pin "2") (pinfunction "2_2") (pintype "passive"))
      (node (ref "R26") (pin "2") (pinfunction "2_2") (pintype "passive"))
      (node (ref "U5") (pin "13") (pinfunction "A0_13") (pintype "passive"))
      (node (ref "U8") (pin "4") (pinfunction "IO3_4") (pintype "bidirectional"))
    )
    (net (code "15") (name "/R_G1") (class "Default")
      (node (ref "R34") (pin "1") (pinfunction "1_1") (pintype "passive"))
      (node (ref "R38") (pin "1") (pinfunction "1_1") (pintype "passive"))
      (node (ref "U6") (pin "13") (pinfunction "A0_13") (pintype "passive"))
      (node (ref "U9") (pin "2") (pinfunction "IO2_2") (pintype "bidirectional"))
    )
    (net (code "16") (name "/R_G2") (class "Default")
      (node (ref "R36") (pin "1") (pinfunction "1_1") (pintype "passive"))
      (node (ref "R39") (pin "1") (pinfunction "1_1") (pintype "passive"))
      (node (ref "U10") (pin "5") (pinfunction "IO4_5") (pintype "bidirectional"))
      (node (ref "U6") (pin "14") (pinfunction "A1_14") (pintype "passive"))
    )
    (net (code "17") (name "/R_G3") (class "Default")
      (node (ref "R32") (pin "2") (pinfunction "2_2") (pintype "passive"))
      (node (ref "R49") (pin "2") (pinfunction "2_2") (pintype "passive"))
      (node (ref "U10") (pin "4") (pinfunction "IO3_4") (pintype "bidirectional"))
      (node (ref "U6") (pin "5") (pinfunction "A5_5") (pintype "passive"))
    )
    (net (code "18") (name "/R_G4") (class "Default")
      (node (ref "R33") (pin "2") (pinfunction "2_2") (pintype "passive"))
      (node (ref "R47") (pin "2") (pinfunction "2_2") (pintype "passive"))
      (node (ref "U10") (pin "1") (pinfunction "IO1_1") (pintype "bidirectional"))
      (node (ref "U6") (pin "1") (pinfunction "A4_1") (pintype "passive"))
    )
    (net (code "19") (name "/R_G5") (class "Default")
      (node (ref "R35") (pin "2") (pinfunction "2_2") (pintype "passive"))
      (node (ref "R45") (pin "2") (pinfunction "2_2") (pintype "passive"))
      (node (ref "U10") (pin "2") (pinfunction "IO2_2") (pintype "bidirectional"))
      (node (ref "U6") (pin "12") (pinfunction "A3_12") (pintype "passive"))
    )
    (net (code "20") (name "/R_G6") (class "Default")
      (node (ref "R37") (pin "2") (pinfunction "2_2") (pintype "passive"))
      (node (ref "R41") (pin "2") (pinfunction "2_2") (pintype "passive"))
      (node (ref "U3") (pin "2") (pinfunction "IO2_2") (pintype "bidirectional"))
      (node (ref "U6") (pin "15") (pinfunction "A2_15") (pintype "passive"))
    )
    (net (code "21") (name "/R_S0") (class "Default")
      (node (ref "R30") (pin "2") (pinfunction "2_2") (pintype "passive"))
      (node (ref "R50") (pin "2") (pinfunction "2_2") (pintype "passive"))
      (node (ref "U6") (pin "2") (pinfunction "A6_2") (pintype "passive"))
      (node (ref "U8") (pin "2") (pinfunction "IO2_2") (pintype "bidirectional"))
    )
    (net (code "22") (name "/R_S1") (class "Default")
      (node (ref "R16") (pin "2") (pinfunction "2_2") (pintype "passive"))
      (node (ref "R27") (pin "1") (pinfunction "1_1") (pintype "passive"))
      (node (ref "U5") (pin "5") (pinfunction "A5_5") (pintype "passive"))
      (node (ref "U8") (pin "1") (pinfunction "IO1_1") (pintype "bidirectional"))
    )
    (net (code "23") (name "/R_S2") (class "Default")
      (node (ref "R28") (pin "2") (pinfunction "2_2") (pintype "passive"))
      (node (ref "R51") (pin "2") (pinfunction "2_2") (pintype "passive"))
      (node (ref "U6") (pin "4") (pinfunction "A7_4") (pintype "passive"))
      (node (ref "U9") (pin "5") (pinfunction "IO4_5") (pintype "bidirectional"))
    )
    (net (code "24") (name "/R_S7") (class "Default")
      (node (ref "R14") (pin "2") (pinfunction "2_2") (pintype "passive"))
      (node (ref "R31") (pin "1") (pinfunction "1_1") (pintype "passive"))
      (node (ref "U5") (pin "4") (pinfunction "A7_4") (pintype "passive"))
      (node (ref "U9") (pin "1") (pinfunction "IO1_1") (pintype "bidirectional"))
    )
    (net (code "25") (name "/R_nRst") (class "Default")
      (node (ref "R15") (pin "2") (pinfunction "2_2") (pintype "passive"))
      (node (ref "R29") (pin "1") (pinfunction "1_1") (pintype "passive"))
      (node (ref "U5") (pin "2") (pinfunction "A6_2") (pintype "passive"))
      (node (ref "U9") (pin "4") (pinfunction "IO3_4") (pintype "bidirectional"))
    )
    (net (code "26") (name "GND") (class "Default")
      (node (ref "C10") (pin "1") (pinfunction "1_1") (pintype "passive"))
      (node (ref "C11") (pin "1") (pinfunction "1_1") (pintype "passive"))
      (node (ref "C12") (pin "1") (pinfunction "1_1") (pintype "passive"))
      (node (ref "C4") (pin "1") (pinfunction "1_1") (pintype "passive"))
      (node (ref "C5") (pin "2") (pinfunction "2_2") (pintype "passive"))
      (node (ref "C6") (pin "1") (pinfunction "1_1") (pintype "passive"))
      (node (ref "C7") (pin "2") (pinfunction "2_2") (pintype "passive"))
      (node (ref "C8") (pin "1") (pinfunction "1_1") (pintype "passive"))
      (node (ref "C9") (pin "1") (pinfunction "1_1") (pintype "passive"))
      (node (ref "D5") (pin "1") (pinfunction "A_1") (pintype "passive"))
      (node (ref "D6") (pin "1") (pinfunction "A_1") (pintype "passive"))
      (node (ref "R14") (pin "1") (pinfunction "1_1") (pintype "passive"))
      (node (ref "R15") (pin "1") (pinfunction "1_1") (pintype "passive"))
      (node (ref "R16") (pin "1") (pinfunction "1_1") (pintype "passive"))
      (node (ref "R17") (pin "1") (pinfunction "1_1") (pintype "passive"))
      (node (ref "R18") (pin "1") (pinfunction "1_1") (pintype "passive"))
      (node (ref "R19") (pin "1") (pinfunction "1_1") (pintype "passive"))
      (node (ref "R20") (pin "1") (pinfunction "1_1") (pintype "passive"))
      (node (ref "R21") (pin "1") (pinfunction "1_1") (pintype "passive"))
      (node (ref "R38") (pin "2") (pinfunction "2_2") (pintype "passive"))
      (node (ref "R39") (pin "2") (pinfunction "2_2") (pintype "passive"))
      (node (ref "R41") (pin "1") (pinfunction "1_1") (pintype "passive"))
      (node (ref "R45") (pin "1") (pinfunction "1_1") (pintype "passive"))
      (node (ref "R47") (pin "1") (pinfunction "1_1") (pintype "passive"))
      (node (ref "R49") (pin "1") (pinfunction "1_1") (pintype "passive"))
      (node (ref "R50") (pin "1") (pinfunction "1_1") (pintype "passive"))
      (node (ref "R51") (pin "1") (pinfunction "1_1") (pintype "passive"))
      (node (ref "U10") (pin "3") (pinfunction "GND_3") (pintype "power_in"))
      (node (ref "U3") (pin "3") (pinfunction "GND_3") (pintype "power_in"))
      (node (ref "U5") (pin "6") (pinfunction "~{E}_6") (pintype "input"))
      (node (ref "U5") (pin "7") (pinfunction "VEE_7") (pintype "power_in"))
      (node (ref "U5") (pin "8") (pinfunction "GND_8") (pintype "power_in"))
      (node (ref "U6") (pin "6") (pinfunction "~{E}_6") (pintype "input"))
      (node (ref "U6") (pin "7") (pinfunction "VEE_7") (pintype "power_in"))
      (node (ref "U6") (pin "8") (pinfunction "GND_8") (pintype "power_in"))
      (node (ref "U7") (pin "3") (pinfunction "GND_3") (pintype "power_in"))
      (node (ref "U8") (pin "3") (pinfunction "GND_3") (pintype "power_in"))
      (node (ref "U9") (pin "3") (pinfunction "GND_3") (pintype "power_in"))
    )
    (net (code "27") (name "Net-(D5-C)") (class "Default")
      (node (ref "C5") (pin "1") (pinfunction "1_1") (pintype "passive"))
      (node (ref "D5") (pin "3") (pinfunction "C_3") (pintype "passive"))
      (node (ref "R111") (pin "1") (pinfunction "1_1") (pintype "passive"))
      (node (ref "R118") (pin "2") (pinfunction "2_2") (pintype "passive"))
    )
    (net (code "28") (name "Net-(D6-C)") (class "Default")
      (node (ref "C7") (pin "1") (pinfunction "1_1") (pintype "passive"))
      (node (ref "D6") (pin "3") (pinfunction "C_3") (pintype "passive"))
      (node (ref "R112") (pin "1") (pinfunction "1_1") (pintype "passive"))
      (node (ref "R119") (pin "2") (pinfunction "2_2") (pintype "passive"))
    )
    (net (code "29") (name "Net-(J5-Pad5)") (class "Default")
      (node (ref "J5") (pin "5") (pinfunction "5_5") (pintype "passive"))
      (node (ref "R22") (pin "2") (pinfunction "2_2") (pintype "passive"))
    )
    (net (code "30") (name "Net-(J5-Pad7)") (class "Default")
      (node (ref "J5") (pin "7") (pinfunction "7_7") (pintype "passive"))
      (node (ref "R23") (pin "2") (pinfunction "2_2") (pintype "passive"))
    )
    (net (code "31") (name "Net-(J5-Pad8)") (class "Default")
      (node (ref "J5") (pin "8") (pinfunction "8_8") (pintype "passive"))
      (node (ref "R24") (pin "1") (pinfunction "1_1") (pintype "passive"))
    )
    (net (code "32") (name "Net-(J5-Pad10)") (class "Default")
      (node (ref "J5") (pin "10") (pinfunction "10_10") (pintype "passive"))
      (node (ref "J5") (pin "12") (pinfunction "12_12") (pintype "passive"))
    )
    (net (code "33") (name "Net-(J5-Pad11)") (class "Default")
      (node (ref "J5") (pin "11") (pinfunction "11_11") (pintype "passive"))
      (node (ref "J5") (pin "9") (pinfunction "9_9") (pintype "passive"))
    )
    (net (code "34") (name "Net-(J5-Pad13)") (class "Default")
      (node (ref "J5") (pin "13") (pinfunction "13_13") (pintype "passive"))
      (node (ref "R25") (pin "2") (pinfunction "2_2") (pintype "passive"))
    )
    (net (code "35") (name "Net-(J5-Pad14)") (class "Default")
      (node (ref "J5") (pin "14") (pinfunction "14_14") (pintype "passive"))
      (node (ref "R26") (pin "1") (pinfunction "1_1") (pintype "passive"))
    )
    (net (code "36") (name "Net-(J5-Pad15)") (class "Default")
      (node (ref "J5") (pin "15") (pinfunction "15_15") (pintype "passive"))
      (node (ref "R27") (pin "2") (pinfunction "2_2") (pintype "passive"))
      (node (ref "R69") (pin "2") (pinfunction "2_2") (pintype "passive"))
    )
    (net (code "37") (name "Net-(J5-Pad16)") (class "Default")
      (node (ref "J5") (pin "16") (pinfunction "16_16") (pintype "passive"))
      (node (ref "R12") (pin "1") (pinfunction "1_1") (pintype "passive"))
      (node (ref "R28") (pin "1") (pinfunction "1_1") (pintype "passive"))
    )
    (net (code "38") (name "Net-(J5-Pad17)") (class "Default")
      (node (ref "J5") (pin "17") (pinfunction "17_17") (pintype "passive"))
      (node (ref "R29") (pin "2") (pinfunction "2_2") (pintype "passive"))
      (node (ref "R68") (pin "2") (pinfunction "2_2") (pintype "passive"))
    )
    (net (code "39") (name "Net-(J5-Pad18)") (class "Default")
      (node (ref "J5") (pin "18") (pinfunction "18_18") (pintype "passive"))
      (node (ref "R11") (pin "1") (pinfunction "1_1") (pintype "passive"))
      (node (ref "R30") (pin "1") (pinfunction "1_1") (pintype "passive"))
    )
    (net (code "40") (name "Net-(J5-Pad19)") (class "Default")
      (node (ref "J5") (pin "19") (pinfunction "19_19") (pintype "passive"))
      (node (ref "R13") (pin "2") (pinfunction "2_2") (pintype "passive"))
      (node (ref "R31") (pin "2") (pinfunction "2_2") (pintype "passive"))
    )
    (net (code "41") (name "Net-(J5-Pad20)") (class "Default")
      (node (ref "J5") (pin "20") (pinfunction "20_20") (pintype "passive"))
      (node (ref "R32") (pin "1") (pinfunction "1_1") (pintype "passive"))
      (node (ref "R40") (pin "2") (pinfunction "2_2") (pintype "passive"))
    )
    (net (code "42") (name "Net-(J5-Pad22)") (class "Default")
      (node (ref "J5") (pin "22") (pinfunction "22_22") (pintype "passive"))
      (node (ref "R33") (pin "1") (pinfunction "1_1") (pintype "passive"))
      (node (ref "R44") (pin "2") (pinfunction "2_2") (pintype "passive"))
    )
    (net (code "43") (name "Net-(J5-Pad23)") (class "Default")
      (node (ref "J5") (pin "23") (pinfunction "23_23") (pintype "passive"))
      (node (ref "R34") (pin "2") (pinfunction "2_2") (pintype "passive"))
      (node (ref "R43") (pin "1") (pinfunction "1_1") (pintype "passive"))
    )
    (net (code "44") (name "Net-(J5-Pad24)") (class "Default")
      (node (ref "J5") (pin "24") (pinfunction "24_24") (pintype "passive"))
      (node (ref "R35") (pin "1") (pinfunction "1_1") (pintype "passive"))
      (node (ref "R46") (pin "2") (pinfunction "2_2") (pintype "passive"))
    )
    (net (code "45") (name "Net-(J5-Pad25)") (class "Default")
      (node (ref "J5") (pin "25") (pinfunction "25_25") (pintype "passive"))
      (node (ref "R36") (pin "2") (pinfunction "2_2") (pintype "passive"))
      (node (ref "R42") (pin "1") (pinfunction "1_1") (pintype "passive"))
    )
    (net (code "46") (name "Net-(J5-Pad26)") (class "Default")
      (node (ref "J5") (pin "26") (pinfunction "26_26") (pintype "passive"))
      (node (ref "R37") (pin "1") (pinfunction "1_1") (pintype "passive"))
      (node (ref "R48") (pin "2") (pinfunction "2_2") (pintype "passive"))
    )
    (net (code "47") (name "Net-(U5-A)") (class "Default")
      (node (ref "R111") (pin "2") (pinfunction "2_2") (pintype "passive"))
      (node (ref "U5") (pin "3") (pinfunction "A_3") (pintype "passive"))
    )
    (net (code "48") (name "Net-(U6-A)") (class "Default")
      (node (ref "R112") (pin "2") (pinfunction "2_2") (pintype "passive"))
      (node (ref "U6") (pin "3") (pinfunction "A_3") (pintype "passive"))
    )
    (net (code "49") (name "unconnected-(J5-Pad1)") (class "Default")
      (node (ref "J5") (pin "1") (pinfunction "1_1") (pintype "passive+no_connect"))
    )
    (net (code "50") (name "unconnected-(J5-Pad2)") (class "Default")
      (node (ref "J5") (pin "2") (pinfunction "2_2") (pintype "passive+no_connect"))
    )
    (net (code "51") (name "unconnected-(J5-Pad4)") (class "Default")
      (node (ref "J5") (pin "4") (pinfunction "4_4") (pintype "passive+no_connect"))
    )
    (net (code "52") (name "unconnected-(J5-Pad21)") (class "Default")
      (node (ref "J5") (pin "21") (pinfunction "21_21") (pintype "passive+no_connect"))
    )
    (net (code "53") (name "unconnected-(U3-IO1-Pad1)") (class "Default")
      (node (ref "U3") (pin "1") (pinfunction "IO1_1") (pintype "bidirectional+no_connect"))
    )
  )
)
